# MainBOB_RUDRV2.net
KiCad netlist of a schematic drawn in Altium Designer
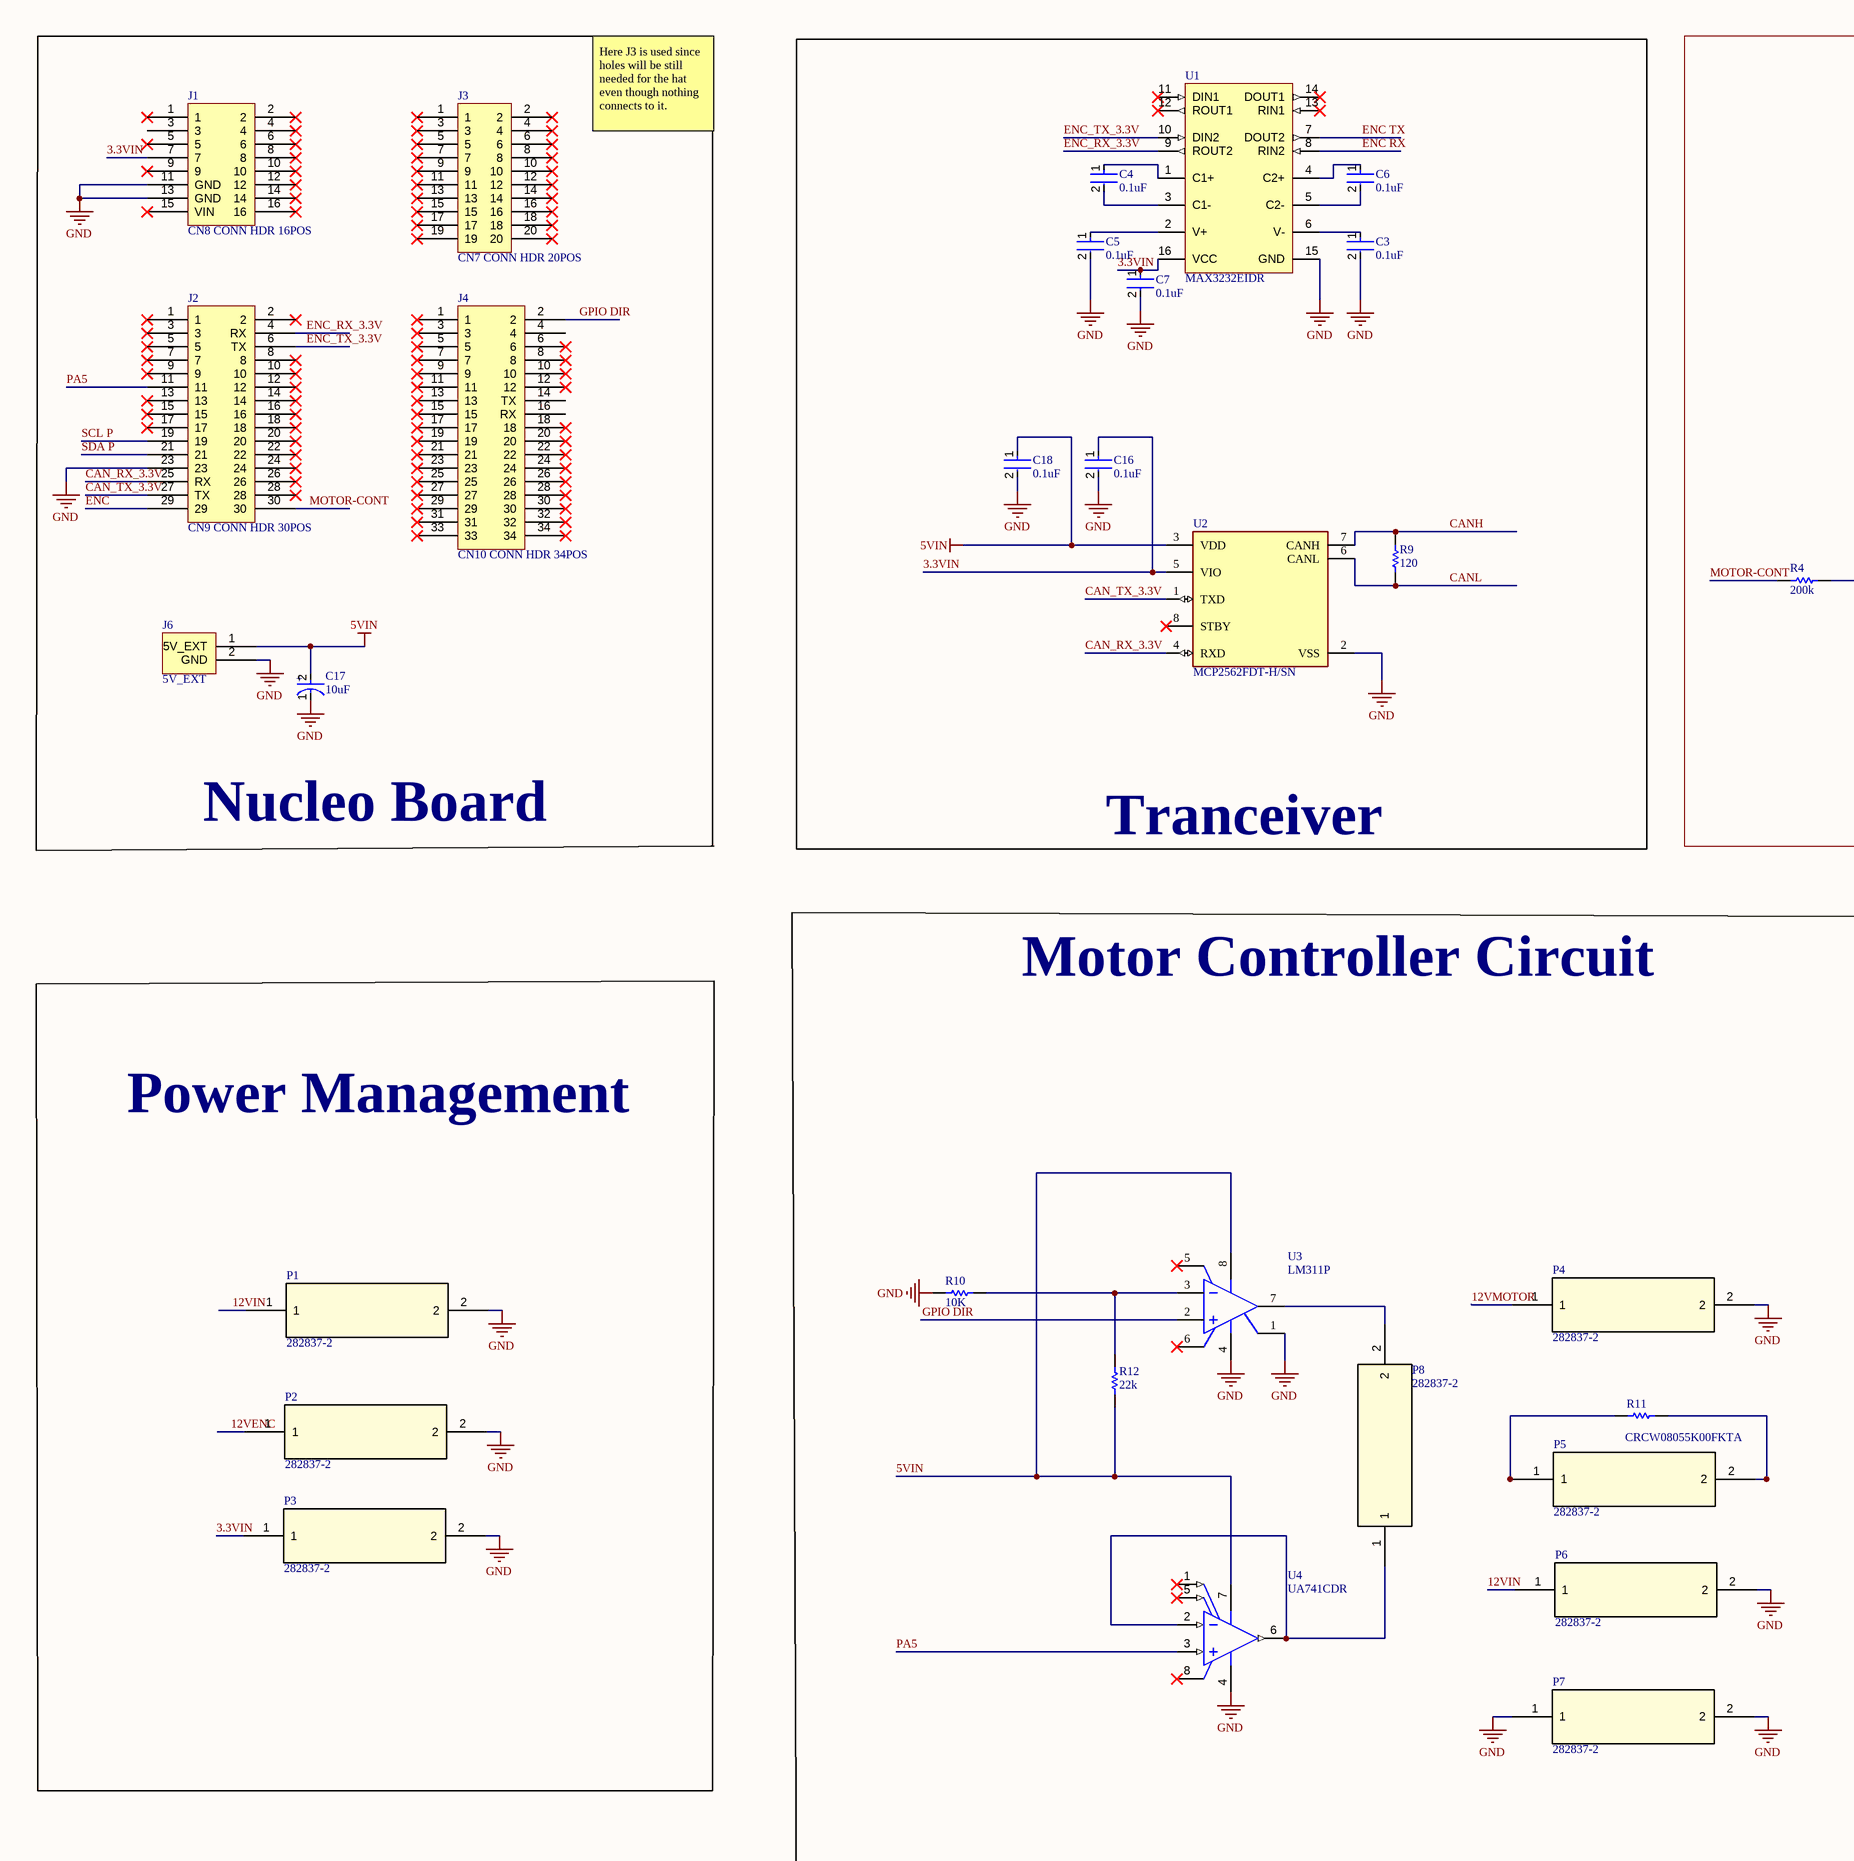
[diagram p0: MainBOB_RUDRV2.SchDoc, left]
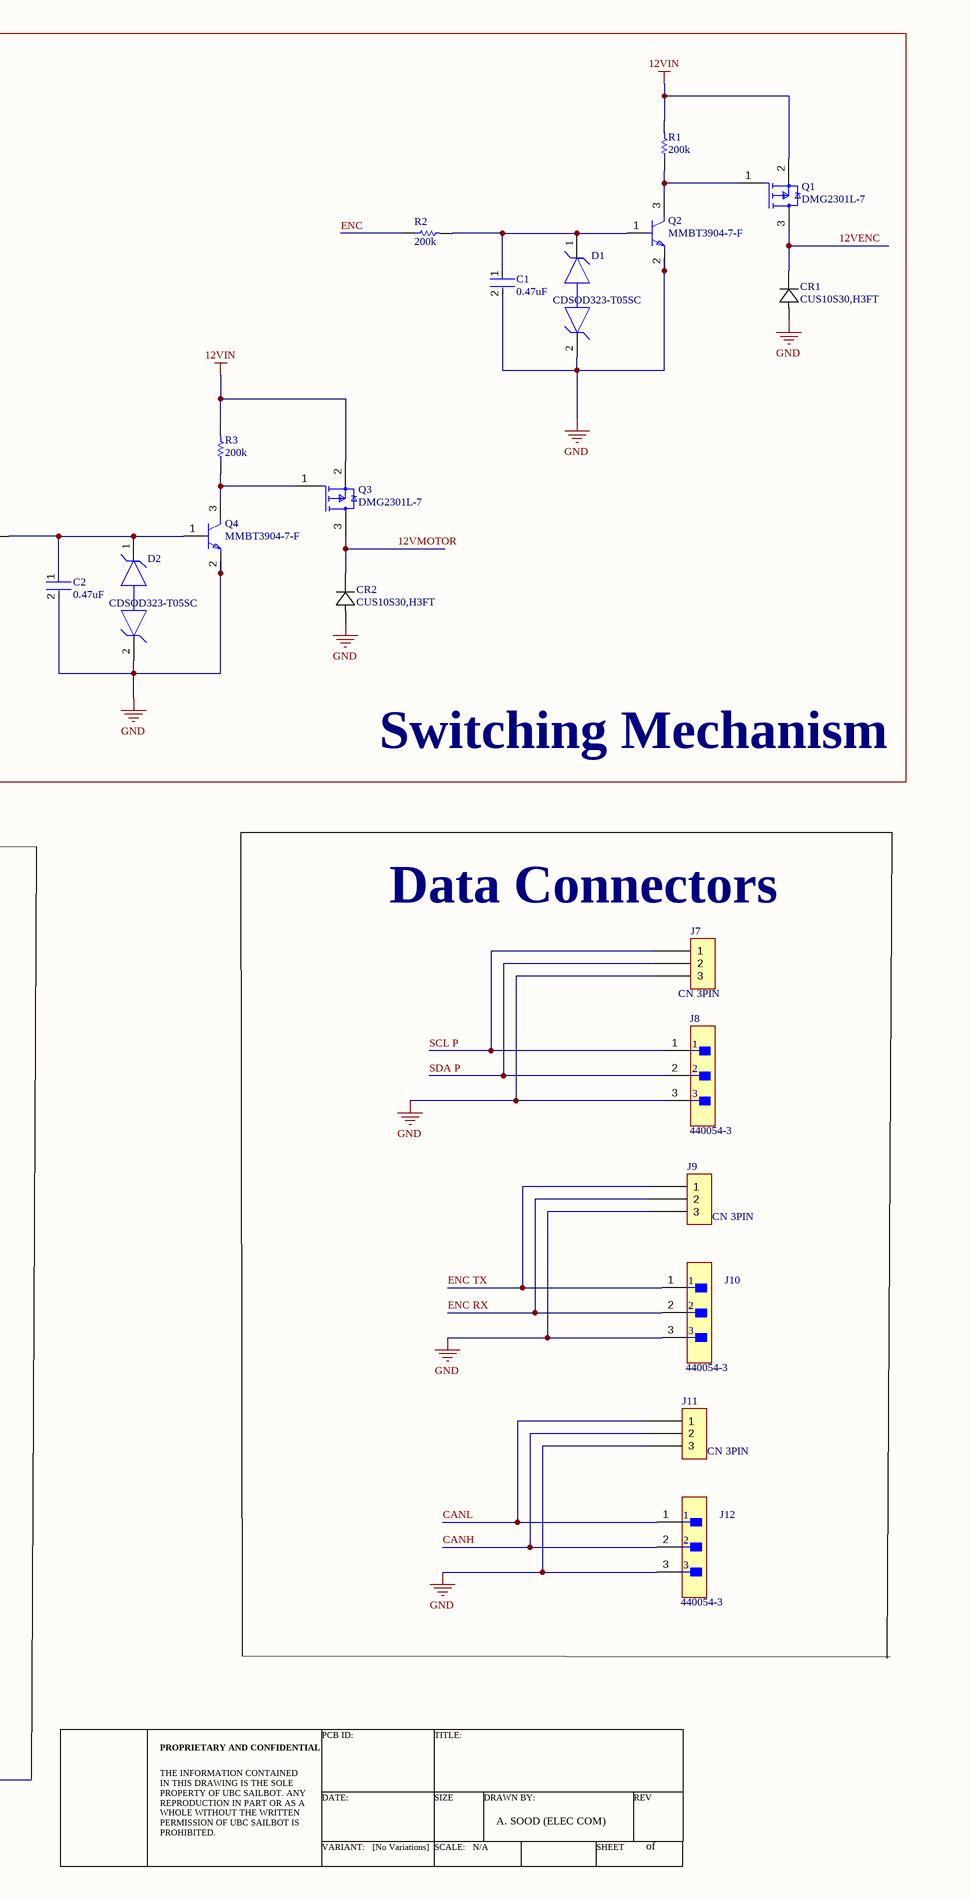
[diagram p1: MainBOB_RUDRV2.SchDoc, right]

(export (version "E")
  (design (tool "Eeschema 10.0.6"))
  (components
    (comp (ref "*") (value "Title Block") (libsource (lib "Schlib1") (part "Title Block")))
    (comp (ref "C1")
      (value "0.47uF")
      (footprint "FP-GRM21B-0_15-IPC_B")
      (description "Chip Multilayer Ceramic Capacitors for General Purpose, 0805, 0.47uF, X7R, 15%, 10%, 100V")
      (fields (field (name "VOLTAGE") "100V") (field (name "TOLERANCE") "10%"))
      (libsource (lib "Altium Content Vault") (part "b4654b650e69147ec39a6b967a45e02"))
    )
    (comp (ref "C2")
      (value "0.47uF")
      (footprint "FP-GRM21B-0_15-IPC_B")
      (description "Chip Multilayer Ceramic Capacitors for General Purpose, 0805, 0.47uF, X7R, 15%, 10%, 100V")
      (fields (field (name "VOLTAGE") "100V") (field (name "TOLERANCE") "10%"))
      (libsource (lib "Altium Content Vault") (part "b4654b650e69147ec39a6b967a45e02"))
    )
    (comp (ref "C3")
      (value "0.1uF")
      (footprint "FP-GCM21B-0_15-MFG")
      (description "Ceramic Capacitor for Automotive 100nF ±10% 100VDC X7R 0805 Embossed T/R")
      (fields (field (name "TOLERANCE") "10%") (field (name "VOLTAGE") "100V"))
      (libsource (lib "Altium Content Vault") (part "02cd4be3c70576c341d710602a673aa"))
    )
    (comp (ref "C4")
      (value "0.1uF")
      (footprint "FP-GCM21B-0_15-MFG")
      (description "Ceramic Capacitor for Automotive 100nF ±10% 100VDC X7R 0805 Embossed T/R")
      (fields (field (name "TOLERANCE") "10%") (field (name "VOLTAGE") "100V"))
      (libsource (lib "Altium Content Vault") (part "02cd4be3c70576c341d710602a673aa"))
    )
    (comp (ref "C5")
      (value "0.1uF")
      (footprint "FP-GCM21B-0_15-MFG")
      (description "Ceramic Capacitor for Automotive 100nF ±10% 100VDC X7R 0805 Embossed T/R")
      (fields (field (name "TOLERANCE") "10%") (field (name "VOLTAGE") "100V"))
      (libsource (lib "Altium Content Vault") (part "02cd4be3c70576c341d710602a673aa"))
    )
    (comp (ref "C6")
      (value "0.1uF")
      (footprint "FP-GCM21B-0_15-MFG")
      (description "Ceramic Capacitor for Automotive 100nF ±10% 100VDC X7R 0805 Embossed T/R")
      (fields (field (name "TOLERANCE") "10%") (field (name "VOLTAGE") "100V"))
      (libsource (lib "Altium Content Vault") (part "02cd4be3c70576c341d710602a673aa"))
    )
    (comp (ref "C7")
      (value "0.1uF")
      (footprint "FP-GCM21B-0_15-MFG")
      (description "Ceramic Capacitor for Automotive 100nF ±10% 100VDC X7R 0805 Embossed T/R")
      (fields (field (name "TOLERANCE") "10%") (field (name "VOLTAGE") "100V"))
      (libsource (lib "Altium Content Vault") (part "02cd4be3c70576c341d710602a673aa"))
    )
    (comp (ref "C16")
      (value "0.1uF")
      (footprint "FP-GCM21B-0_15-MFG")
      (description "Ceramic Capacitor for Automotive 100nF ±10% 100VDC X7R 0805 Embossed T/R")
      (fields (field (name "TOLERANCE") "10%") (field (name "VOLTAGE") "100V"))
      (libsource (lib "Altium Content Vault") (part "02cd4be3c70576c341d710602a673aa"))
    )
    (comp (ref "C17")
      (value "10uF")
      (footprint "FP-FKC-MFG")
      (description "CAP ALUM 10UF 20% 50V SMD")
      (fields (field (name "TOLERANCE") "20%") (field (name "VOLTAGE") "50V"))
      (libsource (lib "Altium Content Vault") (part "a00bbbee19879c290e62620ae7e47b1"))
    )
    (comp (ref "C18")
      (value "0.1uF")
      (footprint "FP-GCM21B-0_15-MFG")
      (description "Ceramic Capacitor for Automotive 100nF ±10% 100VDC X7R 0805 Embossed T/R")
      (fields (field (name "TOLERANCE") "10%") (field (name "VOLTAGE") "100V"))
      (libsource (lib "Altium Content Vault") (part "02cd4be3c70576c341d710602a673aa"))
    )
    (comp (ref "CR1")
      (value "CUS10S30,H3FT")
      (footprint "USC_TOS")
      (description "No Description Available")
      (libsource (lib "Schlib1") (part "CUS10S30,H3FT"))
    )
    (comp (ref "CR2")
      (value "CUS10S30,H3FT")
      (footprint "USC_TOS")
      (description "No Description Available")
      (libsource (lib "Schlib1") (part "CUS10S30,H3FT"))
    )
    (comp (ref "D1")
      (value "CDSOD323-T05SC")
      (footprint "FP-SOD-323-CA-MFG")
      (description "TVS DIODE 5VWM 14.5VC SOD323")
      (libsource (lib "Altium Content Vault") (part "c43c1b0add0eb72e36bdc657e82fc73"))
    )
    (comp (ref "D2")
      (value "CDSOD323-T05SC")
      (footprint "FP-SOD-323-CA-MFG")
      (description "TVS DIODE 5VWM 14.5VC SOD323")
      (libsource (lib "Altium Content Vault") (part "c43c1b0add0eb72e36bdc657e82fc73"))
    )
    (comp (ref "J1")
      (value "CN8 CONN HDR 16POS")
      (footprint "CN8_8X2_PADS")
      (description "CN8 CONN HDR 16POS 0.1 STACK")
      (libsource (lib "Schlib2") (part "CN8 CONN HDR 16POS"))
    )
    (comp (ref "J2")
      (value "CN9 CONN HDR 30POS")
      (footprint "CN9_15X2_PADS")
      (description "CN9 CONN HDR 30 POS  0.1 STACK")
      (libsource (lib "Schlib2") (part "CN9 CONN HDR 30POS"))
    )
    (comp (ref "J3")
      (value "CN7 CONN HDR 20POS")
      (footprint "CN7_10X2_PADS")
      (description "CN7 CONN HDR 20 POS  0.1 STACK")
      (libsource (lib "Schlib2") (part "CN7 CONN HDR 20POS"))
    )
    (comp (ref "J4")
      (value "CN10 CONN HDR 34POS")
      (footprint "CN10_17X2_PADS")
      (description "CN10 CONN HDR 34 POS  0.1 STACK")
      (libsource (lib "Schlib1") (part "CN10 CONN HDR 34POS"))
    )
    (comp (ref "J6") (value "5V_EXT") (footprint "5V_EXT") (libsource (lib "Schlib2") (part "5V_EXT")))
    (comp (ref "J7") (value "CN 3PIN") (footprint "3X1 CON") (libsource (lib "Schlib2") (part "CN 3PIN")))
    (comp (ref "J8")
      (value "440054-3")
      (footprint "FP-440054-3-MFG")
      (description "CONN HEADER VERT 3POS 2MM")
      (fields
        (field (name "OCTOPART") "https://octopart.com/440054-3-te+connectivity-40394845")
        (field (name "MANUFACTURER") "TE Connectivity")
      )
      (libsource (lib "Altium Content Vault") (part "0d3f023dd272f625e17a2be33dea85f"))
    )
    (comp (ref "J9") (value "CN 3PIN") (footprint "3X1 CON") (libsource (lib "Schlib2") (part "CN 3PIN")))
    (comp (ref "J10")
      (value "440054-3")
      (footprint "FP-440054-3-MFG")
      (description "CONN HEADER VERT 3POS 2MM")
      (fields
        (field (name "OCTOPART") "https://octopart.com/440054-3-te+connectivity-40394845")
        (field (name "MANUFACTURER") "TE Connectivity")
      )
      (libsource (lib "Altium Content Vault") (part "0d3f023dd272f625e17a2be33dea85f"))
    )
    (comp (ref "J11") (value "CN 3PIN") (footprint "3X1 CON") (libsource (lib "Schlib2") (part "CN 3PIN")))
    (comp (ref "J12")
      (value "440054-3")
      (footprint "FP-440054-3-MFG")
      (description "CONN HEADER VERT 3POS 2MM")
      (fields
        (field (name "OCTOPART") "https://octopart.com/440054-3-te+connectivity-40394845")
        (field (name "MANUFACTURER") "TE Connectivity")
      )
      (libsource (lib "Altium Content Vault") (part "0d3f023dd272f625e17a2be33dea85f"))
    )
    (comp (ref "P1")
      (value "282837-2")
      (footprint "282837-2_TYC")
      (description "No Description Available")
      (libsource (lib "Schlib1") (part "282837-2"))
    )
    (comp (ref "P2")
      (value "282837-2")
      (footprint "282837-2_TYC")
      (description "No Description Available")
      (libsource (lib "Schlib1") (part "282837-2"))
    )
    (comp (ref "P3")
      (value "282837-2")
      (footprint "282837-2_TYC")
      (description "No Description Available")
      (libsource (lib "Schlib1") (part "282837-2"))
    )
    (comp (ref "P4")
      (value "282837-2")
      (footprint "282837-2_TYC")
      (description "No Description Available")
      (libsource (lib "Schlib1") (part "282837-2"))
    )
    (comp (ref "P5")
      (value "282837-2")
      (footprint "282837-2_TYC")
      (description "No Description Available")
      (libsource (lib "Schlib1") (part "282837-2"))
    )
    (comp (ref "P6")
      (value "282837-2")
      (footprint "282837-2_TYC")
      (description "No Description Available")
      (libsource (lib "Schlib1") (part "282837-2"))
    )
    (comp (ref "P7")
      (value "282837-2")
      (footprint "282837-2_TYC")
      (description "No Description Available")
      (libsource (lib "Schlib1") (part "282837-2"))
    )
    (comp (ref "P8")
      (value "282837-2")
      (footprint "282837-2_TYC")
      (description "No Description Available")
      (libsource (lib "") (part "282837-2_1"))
    )
    (comp (ref "Q1")
      (value "DMG2301L-7")
      (footprint "FP-SOT23-MFG")
      (description "MOSFET P-CH 20V 3A SOT23")
      (fields
        (field (name "MANUFACTURER") "Diodes Inc.")
        (field (name "OCTOPART") "https://octopart.com/dmg2301l-7-diodes+inc.-67250456")
      )
      (libsource (lib "Altium Content Vault") (part "b8f99f9e586195791e7fb11725ebaeb"))
    )
    (comp (ref "Q2")
      (value "MMBT3904-7-F")
      (footprint "FP-SOT23-IPC_A")
      (description "TRANS NPN 40V 0.2A SMD SOT23-3")
      (libsource (lib "Altium Content Vault") (part "b44e953556f554d0102664c7d152cb4"))
    )
    (comp (ref "Q3")
      (value "DMG2301L-7")
      (footprint "FP-SOT23-MFG")
      (description "MOSFET P-CH 20V 3A SOT23")
      (fields
        (field (name "MANUFACTURER") "Diodes Inc.")
        (field (name "OCTOPART") "https://octopart.com/dmg2301l-7-diodes+inc.-67250456")
      )
      (libsource (lib "Altium Content Vault") (part "b8f99f9e586195791e7fb11725ebaeb"))
    )
    (comp (ref "Q4")
      (value "MMBT3904-7-F")
      (footprint "FP-SOT23-IPC_A")
      (description "TRANS NPN 40V 0.2A SMD SOT23-3")
      (libsource (lib "Altium Content Vault") (part "b44e953556f554d0102664c7d152cb4"))
    )
    (comp (ref "R1")
      (value "200k")
      (footprint "RESC2013X70X40LL20T20")
      (fields (field (name "MANUFACTURER") "Panasonic") (field (name "PART NUMBER") "ERJ-6ENF2003V"))
      (libsource (lib "Altium Content Vault") (part "RES"))
    )
    (comp (ref "R2")
      (value "200k")
      (footprint "RESC2013X70X40LL20T20")
      (fields (field (name "MANUFACTURER") "Panasonic") (field (name "PART NUMBER") "ERJ-6ENF2003V"))
      (libsource (lib "Altium Content Vault") (part "RES"))
    )
    (comp (ref "R3")
      (value "200k")
      (footprint "RESC2013X70X40LL20T20")
      (fields (field (name "MANUFACTURER") "Panasonic") (field (name "PART NUMBER") "ERJ-6ENF2003V"))
      (libsource (lib "Altium Content Vault") (part "RES"))
    )
    (comp (ref "R4")
      (value "200k")
      (footprint "RESC2013X70X40LL20T20")
      (fields (field (name "MANUFACTURER") "Panasonic") (field (name "PART NUMBER") "ERJ-6ENF2003V"))
      (libsource (lib "Altium Content Vault") (part "RES"))
    )
    (comp (ref "R9")
      (value "120")
      (footprint "RESC2013X60X35ML10T20")
      (description "Chip Resistor, 1 KOhm, +/- 1%, 125 mW, -55 to 155 degC, 0805 (2012 Metric), RoHS, Tape and Reel")
      (fields (field (name "TOLERANCE") "1%") (field (name "MANUFACTURER") "Yageo"))
      (libsource (lib "Altium Content Vault") (part "RES-2"))
    )
    (comp (ref "R10")
      (value "10K")
      (footprint "RESC2013X60X40LL20T25_A")
      (fields (field (name "TOLERANCE") "0.1%") (field (name "MANUFACTURER") "Panasonic"))
      (libsource (lib "Altium Content Vault") (part "RES-2"))
    )
    (comp (ref "R11")
      (value "CRCW08055K00FKTA")
      (footprint "RESC2013X50X30ML20T20")
      (fields (field (name "MANUFACTURER") "Vishay Dale"))
      (libsource (lib "Altium Content Vault") (part "RES"))
    )
    (comp (ref "R12")
      (value "22k")
      (footprint "RESC2013X60X40ML20T25")
      (fields (field (name "MANUFACTURER") "Panasonic") (field (name "PART NUMBER") "ERA6AEB223V"))
      (libsource (lib "Altium Content Vault") (part "RES"))
    )
    (comp (ref "U1")
      (value "MAX3232EIDR")
      (footprint "D0016A_N")
      (libsource (lib "Altium Content Vault") (part "TI-MAX3232E-SOIC_D-16"))
    )
    (comp (ref "U2")
      (value "MCP2562FDT-H/SN")
      (footprint "FP-C04-057-SN-IPC_A")
      (description "IC TRANSCEIVER 1/1 8SOIC")
      (libsource (lib "Altium Content Vault") (part "d4eccbb03d796c5d2cef85367bb866b"))
    )
    (comp (ref "U3")
      (value "LM311P")
      (footprint "FP-P0008A-MFG")
      (fields (field (name "TOLERANCE") "1%"))
      (libsource (lib "Altium Content Vault") (part "b2b1c66385073ed7f685b7e01cc60c1"))
    )
    (comp (ref "U4")
      (value "UA741CDR")
      (footprint "D0008A_L")
      (fields (field (name "MANUFACTURER") "Texas Instruments"))
      (libsource (lib "Altium Content Vault") (part "TI-AMP-S5-2-8"))
    )
  )
  (nets
    (net (code "1") (name "/3.3VIN") (class "Default")
      (node (ref "C16") (pin "1") (pinfunction "1_1") (pintype "passive"))
      (node (ref "C7") (pin "1") (pinfunction "1_1") (pintype "passive"))
      (node (ref "J1") (pin "7") (pinfunction "7_7") (pintype "passive"))
      (node (ref "P3") (pin "1") (pinfunction "1_1") (pintype "passive"))
      (node (ref "U1") (pin "16") (pinfunction "VCC_16") (pintype "power_in"))
      (node (ref "U2") (pin "5") (pinfunction "VIO_5") (pintype "power_in"))
    )
    (net (code "2") (name "/12VENC") (class "Default")
      (node (ref "CR1") (pin "1") (pinfunction "cathode_1") (pintype "passive"))
      (node (ref "P2") (pin "1") (pinfunction "1_1") (pintype "passive"))
      (node (ref "Q1") (pin "3") (pinfunction "D_3") (pintype "passive"))
    )
    (net (code "3") (name "/12VMOTOR") (class "Default")
      (node (ref "CR2") (pin "1") (pinfunction "cathode_1") (pintype "passive"))
      (node (ref "P4") (pin "1") (pinfunction "1_1") (pintype "passive"))
      (node (ref "Q3") (pin "3") (pinfunction "D_3") (pintype "passive"))
    )
    (net (code "4") (name "/CANH") (class "Default")
      (node (ref "J11") (pin "2") (pinfunction "2_2") (pintype "passive"))
      (node (ref "J12") (pin "2") (pinfunction "2_2") (pintype "passive"))
      (node (ref "R9") (pin "1") (pinfunction "1_1") (pintype "passive"))
      (node (ref "U2") (pin "7") (pinfunction "CANH_7") (pintype "passive"))
    )
    (net (code "5") (name "/CANL") (class "Default")
      (node (ref "J11") (pin "1") (pinfunction "1_1") (pintype "passive"))
      (node (ref "J12") (pin "1") (pinfunction "1_1") (pintype "passive"))
      (node (ref "R9") (pin "2") (pinfunction "2_2") (pintype "passive"))
      (node (ref "U2") (pin "6") (pinfunction "CANL_6") (pintype "passive"))
    )
    (net (code "6") (name "/CAN_RX_3.3V") (class "Default")
      (node (ref "J2") (pin "25") (pinfunction "RX_25") (pintype "passive"))
      (node (ref "U2") (pin "4") (pinfunction "RXD_4") (pintype "bidirectional"))
    )
    (net (code "7") (name "/CAN_TX_3.3V") (class "Default")
      (node (ref "J2") (pin "27") (pinfunction "TX_27") (pintype "passive"))
      (node (ref "U2") (pin "1") (pinfunction "TXD_1") (pintype "bidirectional"))
    )
    (net (code "8") (name "/ENC") (class "Default")
      (node (ref "J2") (pin "29") (pinfunction "29_29") (pintype "passive"))
      (node (ref "R2") (pin "1") (pinfunction "1_1") (pintype "passive"))
    )
    (net (code "9") (name "/ENC RX") (class "Default")
      (node (ref "J10") (pin "2") (pinfunction "2_2") (pintype "passive"))
      (node (ref "J9") (pin "2") (pinfunction "2_2") (pintype "passive"))
      (node (ref "U1") (pin "8") (pinfunction "RIN2_8") (pintype "input"))
    )
    (net (code "10") (name "/ENC TX") (class "Default")
      (node (ref "J10") (pin "1") (pinfunction "1_1") (pintype "passive"))
      (node (ref "J9") (pin "1") (pinfunction "1_1") (pintype "passive"))
      (node (ref "U1") (pin "7") (pinfunction "DOUT2_7") (pintype "output"))
    )
    (net (code "11") (name "/ENC_RX_3.3V") (class "Default")
      (node (ref "J2") (pin "4") (pinfunction "RX_4") (pintype "passive"))
      (node (ref "U1") (pin "9") (pinfunction "ROUT2_9") (pintype "output"))
    )
    (net (code "12") (name "/ENC_TX_3.3V") (class "Default")
      (node (ref "J2") (pin "6") (pinfunction "TX_6") (pintype "passive"))
      (node (ref "U1") (pin "10") (pinfunction "DIN2_10") (pintype "input"))
    )
    (net (code "13") (name "/GPIO DIR") (class "Default")
      (node (ref "J4") (pin "2") (pinfunction "2_2") (pintype "passive"))
      (node (ref "U3") (pin "2") (pinfunction "IN+_2") (pintype "tri_state"))
    )
    (net (code "14") (name "/MOTOR-CONT") (class "Default")
      (node (ref "J2") (pin "30") (pinfunction "30_30") (pintype "passive"))
      (node (ref "R4") (pin "1") (pinfunction "1_1") (pintype "passive"))
    )
    (net (code "15") (name "/PA5") (class "Default")
      (node (ref "J2") (pin "11") (pinfunction "11_11") (pintype "passive"))
      (node (ref "U4") (pin "3") (pinfunction "IN+_3") (pintype "input"))
    )
    (net (code "16") (name "/SCL P") (class "Default")
      (node (ref "J2") (pin "19") (pinfunction "19_19") (pintype "passive"))
      (node (ref "J7") (pin "1") (pinfunction "1_1") (pintype "passive"))
      (node (ref "J8") (pin "1") (pinfunction "1_1") (pintype "passive"))
    )
    (net (code "17") (name "/SDA P") (class "Default")
      (node (ref "J2") (pin "21") (pinfunction "21_21") (pintype "passive"))
      (node (ref "J7") (pin "2") (pinfunction "2_2") (pintype "passive"))
      (node (ref "J8") (pin "2") (pinfunction "2_2") (pintype "passive"))
    )
    (net (code "18") (name "5VIN") (class "Default")
      (node (ref "C17") (pin "2") (pinfunction "A_2") (pintype "passive"))
      (node (ref "C18") (pin "1") (pinfunction "1_1") (pintype "passive"))
      (node (ref "J6") (pin "1") (pinfunction "5V_EXT_1") (pintype "passive"))
      (node (ref "R12") (pin "1") (pinfunction "1_1") (pintype "passive"))
      (node (ref "U2") (pin "3") (pinfunction "VDD_3") (pintype "power_in"))
      (node (ref "U3") (pin "8") (pinfunction "VCC+_8") (pintype "power_in"))
      (node (ref "U4") (pin "7") (pinfunction "VCC+_7") (pintype "power_in"))
    )
    (net (code "19") (name "12VIN") (class "Default")
      (node (ref "P1") (pin "1") (pinfunction "1_1") (pintype "passive"))
      (node (ref "P6") (pin "1") (pinfunction "1_1") (pintype "passive"))
      (node (ref "Q1") (pin "2") (pinfunction "S_2") (pintype "passive"))
      (node (ref "Q3") (pin "2") (pinfunction "S_2") (pintype "passive"))
      (node (ref "R1") (pin "2") (pinfunction "2_2") (pintype "passive"))
      (node (ref "R3") (pin "2") (pinfunction "2_2") (pintype "passive"))
    )
    (net (code "20") (name "GND") (class "Default")
      (node (ref "C1") (pin "2") (pinfunction "2_2") (pintype "passive"))
      (node (ref "C16") (pin "2") (pinfunction "2_2") (pintype "passive"))
      (node (ref "C17") (pin "1") (pinfunction "C_1") (pintype "passive"))
      (node (ref "C18") (pin "2") (pinfunction "2_2") (pintype "passive"))
      (node (ref "C2") (pin "2") (pinfunction "2_2") (pintype "passive"))
      (node (ref "C3") (pin "2") (pinfunction "2_2") (pintype "passive"))
      (node (ref "C5") (pin "2") (pinfunction "2_2") (pintype "passive"))
      (node (ref "C7") (pin "2") (pinfunction "2_2") (pintype "passive"))
      (node (ref "CR1") (pin "2") (pinfunction "anode_2") (pintype "passive"))
      (node (ref "CR2") (pin "2") (pinfunction "anode_2") (pintype "passive"))
      (node (ref "D1") (pin "2") (pinfunction "2_2") (pintype "passive"))
      (node (ref "D2") (pin "2") (pinfunction "2_2") (pintype "passive"))
      (node (ref "J1") (pin "11") (pinfunction "GND_11") (pintype "passive"))
      (node (ref "J1") (pin "13") (pinfunction "GND_13") (pintype "passive"))
      (node (ref "J10") (pin "3") (pinfunction "3_3") (pintype "passive"))
      (node (ref "J11") (pin "3") (pinfunction "3_3") (pintype "passive"))
      (node (ref "J12") (pin "3") (pinfunction "3_3") (pintype "passive"))
      (node (ref "J2") (pin "23") (pinfunction "23_23") (pintype "passive"))
      (node (ref "J6") (pin "2") (pinfunction "GND_2") (pintype "passive"))
      (node (ref "J7") (pin "3") (pinfunction "3_3") (pintype "passive"))
      (node (ref "J8") (pin "3") (pinfunction "3_3") (pintype "passive"))
      (node (ref "J9") (pin "3") (pinfunction "3_3") (pintype "passive"))
      (node (ref "P1") (pin "2") (pinfunction "2_2") (pintype "passive"))
      (node (ref "P2") (pin "2") (pinfunction "2_2") (pintype "passive"))
      (node (ref "P3") (pin "2") (pinfunction "2_2") (pintype "passive"))
      (node (ref "P4") (pin "2") (pinfunction "2_2") (pintype "passive"))
      (node (ref "P6") (pin "2") (pinfunction "2_2") (pintype "passive"))
      (node (ref "P7") (pin "1") (pinfunction "1_1") (pintype "passive"))
      (node (ref "P7") (pin "2") (pinfunction "2_2") (pintype "passive"))
      (node (ref "Q2") (pin "2") (pinfunction "E_2") (pintype "passive"))
      (node (ref "Q4") (pin "2") (pinfunction "E_2") (pintype "passive"))
      (node (ref "R10") (pin "1") (pinfunction "1_1") (pintype "passive"))
      (node (ref "U1") (pin "15") (pinfunction "GND_15") (pintype "power_in"))
      (node (ref "U2") (pin "2") (pinfunction "VSS_2") (pintype "power_in"))
      (node (ref "U3") (pin "1") (pinfunction "EMIT_OUT_1") (pintype "open_emitter"))
      (node (ref "U3") (pin "4") (pinfunction "VCC-_4") (pintype "power_in"))
      (node (ref "U4") (pin "4") (pinfunction "VCC-_4") (pintype "power_in"))
    )
    (net (code "21") (name "Net-(P5-Pad1)") (class "Default")
      (node (ref "P5") (pin "1") (pinfunction "1_1") (pintype "passive"))
      (node (ref "R11") (pin "1") (pinfunction "1_1") (pintype "passive"))
    )
    (net (code "22") (name "Net-(P5-Pad2)") (class "Default")
      (node (ref "P5") (pin "2") (pinfunction "2_2") (pintype "passive"))
      (node (ref "R11") (pin "2") (pinfunction "2_2") (pintype "passive"))
    )
    (net (code "23") (name "Net-(Q1-G)") (class "Default")
      (node (ref "Q1") (pin "1") (pinfunction "G_1") (pintype "passive"))
      (node (ref "Q2") (pin "3") (pinfunction "C_3") (pintype "passive"))
      (node (ref "R1") (pin "1") (pinfunction "1_1") (pintype "passive"))
    )
    (net (code "24") (name "Net-(Q2-B)") (class "Default")
      (node (ref "C1") (pin "1") (pinfunction "1_1") (pintype "passive"))
      (node (ref "D1") (pin "1") (pinfunction "1_1") (pintype "passive"))
      (node (ref "Q2") (pin "1") (pinfunction "B_1") (pintype "passive"))
      (node (ref "R2") (pin "2") (pinfunction "2_2") (pintype "passive"))
    )
    (net (code "25") (name "Net-(Q3-G)") (class "Default")
      (node (ref "Q3") (pin "1") (pinfunction "G_1") (pintype "passive"))
      (node (ref "Q4") (pin "3") (pinfunction "C_3") (pintype "passive"))
      (node (ref "R3") (pin "1") (pinfunction "1_1") (pintype "passive"))
    )
    (net (code "26") (name "Net-(Q4-B)") (class "Default")
      (node (ref "C2") (pin "1") (pinfunction "1_1") (pintype "passive"))
      (node (ref "D2") (pin "1") (pinfunction "1_1") (pintype "passive"))
      (node (ref "Q4") (pin "1") (pinfunction "B_1") (pintype "passive"))
      (node (ref "R4") (pin "2") (pinfunction "2_2") (pintype "passive"))
    )
    (net (code "27") (name "Net-(U1-C1+)") (class "Default")
      (node (ref "C4") (pin "1") (pinfunction "1_1") (pintype "passive"))
      (node (ref "U1") (pin "1") (pinfunction "C1+_1") (pintype "passive"))
    )
    (net (code "28") (name "Net-(U1-C1-)") (class "Default")
      (node (ref "C4") (pin "2") (pinfunction "2_2") (pintype "passive"))
      (node (ref "U1") (pin "3") (pinfunction "C1-_3") (pintype "passive"))
    )
    (net (code "29") (name "Net-(U1-C2+)") (class "Default")
      (node (ref "C6") (pin "1") (pinfunction "1_1") (pintype "passive"))
      (node (ref "U1") (pin "4") (pinfunction "C2+_4") (pintype "passive"))
    )
    (net (code "30") (name "Net-(U1-C2-)") (class "Default")
      (node (ref "C6") (pin "2") (pinfunction "2_2") (pintype "passive"))
      (node (ref "U1") (pin "5") (pinfunction "C2-_5") (pintype "passive"))
    )
    (net (code "31") (name "Net-(U1-V+)") (class "Default")
      (node (ref "C5") (pin "1") (pinfunction "1_1") (pintype "passive"))
      (node (ref "U1") (pin "2") (pinfunction "V+_2") (pintype "power_in"))
    )
    (net (code "32") (name "Net-(U1-V-)") (class "Default")
      (node (ref "C3") (pin "1") (pinfunction "1_1") (pintype "passive"))
      (node (ref "U1") (pin "6") (pinfunction "V-_6") (pintype "power_in"))
    )
    (net (code "33") (name "Net-(U3-COL_OUT)") (class "Default")
      (node (ref "P8") (pin "2") (pinfunction "2_2") (pintype "passive"))
      (node (ref "U3") (pin "7") (pinfunction "COL_OUT_7") (pintype "open_collector"))
    )
    (net (code "34") (name "Net-(U3-IN-)") (class "Default")
      (node (ref "R10") (pin "2") (pinfunction "2_2") (pintype "passive"))
      (node (ref "R12") (pin "2") (pinfunction "2_2") (pintype "passive"))
      (node (ref "U3") (pin "3") (pinfunction "IN-_3") (pintype "tri_state"))
    )
    (net (code "35") (name "Net-(U4-IN-)") (class "Default")
      (node (ref "P8") (pin "1") (pinfunction "1_1") (pintype "passive"))
      (node (ref "U4") (pin "2") (pinfunction "IN-_2") (pintype "input"))
      (node (ref "U4") (pin "6") (pinfunction "OUT_6") (pintype "output"))
    )
    (net (code "36") (name "unconnected-(J1-Pad1)") (class "Default")
      (node (ref "J1") (pin "1") (pinfunction "1_1") (pintype "passive+no_connect"))
    )
    (net (code "37") (name "unconnected-(J1-Pad2)") (class "Default")
      (node (ref "J1") (pin "2") (pinfunction "2_2") (pintype "passive+no_connect"))
    )
    (net (code "38") (name "unconnected-(J1-Pad3)") (class "Default")
      (node (ref "J1") (pin "3") (pinfunction "3_3") (pintype "passive"))
    )
    (net (code "39") (name "unconnected-(J1-Pad4)") (class "Default")
      (node (ref "J1") (pin "4") (pinfunction "4_4") (pintype "passive+no_connect"))
    )
    (net (code "40") (name "unconnected-(J1-Pad5)") (class "Default")
      (node (ref "J1") (pin "5") (pinfunction "5_5") (pintype "passive+no_connect"))
    )
    (net (code "41") (name "unconnected-(J1-Pad6)") (class "Default")
      (node (ref "J1") (pin "6") (pinfunction "6_6") (pintype "passive+no_connect"))
    )
    (net (code "42") (name "unconnected-(J1-Pad8)") (class "Default")
      (node (ref "J1") (pin "8") (pinfunction "8_8") (pintype "passive+no_connect"))
    )
    (net (code "43") (name "unconnected-(J1-Pad9)") (class "Default")
      (node (ref "J1") (pin "9") (pinfunction "9_9") (pintype "passive+no_connect"))
    )
    (net (code "44") (name "unconnected-(J1-Pad10)") (class "Default")
      (node (ref "J1") (pin "10") (pinfunction "10_10") (pintype "passive+no_connect"))
    )
    (net (code "45") (name "unconnected-(J1-Pad12)") (class "Default")
      (node (ref "J1") (pin "12") (pinfunction "12_12") (pintype "passive+no_connect"))
    )
    (net (code "46") (name "unconnected-(J1-Pad14)") (class "Default")
      (node (ref "J1") (pin "14") (pinfunction "14_14") (pintype "passive+no_connect"))
    )
    (net (code "47") (name "unconnected-(J1-Pad16)") (class "Default")
      (node (ref "J1") (pin "16") (pinfunction "16_16") (pintype "passive+no_connect"))
    )
    (net (code "48") (name "unconnected-(J1-VIN-Pad15)") (class "Default")
      (node (ref "J1") (pin "15") (pinfunction "VIN_15") (pintype "passive+no_connect"))
    )
    (net (code "49") (name "unconnected-(J2-Pad1)") (class "Default")
      (node (ref "J2") (pin "1") (pinfunction "1_1") (pintype "passive+no_connect"))
    )
    (net (code "50") (name "unconnected-(J2-Pad2)") (class "Default")
      (node (ref "J2") (pin "2") (pinfunction "2_2") (pintype "passive+no_connect"))
    )
    (net (code "51") (name "unconnected-(J2-Pad3)") (class "Default")
      (node (ref "J2") (pin "3") (pinfunction "3_3") (pintype "passive+no_connect"))
    )
    (net (code "52") (name "unconnected-(J2-Pad5)") (class "Default")
      (node (ref "J2") (pin "5") (pinfunction "5_5") (pintype "passive+no_connect"))
    )
    (net (code "53") (name "unconnected-(J2-Pad7)") (class "Default")
      (node (ref "J2") (pin "7") (pinfunction "7_7") (pintype "passive+no_connect"))
    )
    (net (code "54") (name "unconnected-(J2-Pad8)") (class "Default")
      (node (ref "J2") (pin "8") (pinfunction "8_8") (pintype "passive+no_connect"))
    )
    (net (code "55") (name "unconnected-(J2-Pad9)") (class "Default")
      (node (ref "J2") (pin "9") (pinfunction "9_9") (pintype "passive+no_connect"))
    )
    (net (code "56") (name "unconnected-(J2-Pad10)") (class "Default")
      (node (ref "J2") (pin "10") (pinfunction "10_10") (pintype "passive+no_connect"))
    )
    (net (code "57") (name "unconnected-(J2-Pad12)") (class "Default")
      (node (ref "J2") (pin "12") (pinfunction "12_12") (pintype "passive+no_connect"))
    )
    (net (code "58") (name "unconnected-(J2-Pad13)") (class "Default")
      (node (ref "J2") (pin "13") (pinfunction "13_13") (pintype "passive+no_connect"))
    )
    (net (code "59") (name "unconnected-(J2-Pad14)") (class "Default")
      (node (ref "J2") (pin "14") (pinfunction "14_14") (pintype "passive+no_connect"))
    )
    (net (code "60") (name "unconnected-(J2-Pad15)") (class "Default")
      (node (ref "J2") (pin "15") (pinfunction "15_15") (pintype "passive+no_connect"))
    )
    (net (code "61") (name "unconnected-(J2-Pad16)") (class "Default")
      (node (ref "J2") (pin "16") (pinfunction "16_16") (pintype "passive+no_connect"))
    )
    (net (code "62") (name "unconnected-(J2-Pad17)") (class "Default")
      (node (ref "J2") (pin "17") (pinfunction "17_17") (pintype "passive+no_connect"))
    )
    (net (code "63") (name "unconnected-(J2-Pad18)") (class "Default")
      (node (ref "J2") (pin "18") (pinfunction "18_18") (pintype "passive+no_connect"))
    )
    (net (code "64") (name "unconnected-(J2-Pad20)") (class "Default")
      (node (ref "J2") (pin "20") (pinfunction "20_20") (pintype "passive+no_connect"))
    )
    (net (code "65") (name "unconnected-(J2-Pad22)") (class "Default")
      (node (ref "J2") (pin "22") (pinfunction "22_22") (pintype "passive+no_connect"))
    )
    (net (code "66") (name "unconnected-(J2-Pad24)") (class "Default")
      (node (ref "J2") (pin "24") (pinfunction "24_24") (pintype "passive+no_connect"))
    )
    (net (code "67") (name "unconnected-(J2-Pad26)") (class "Default")
      (node (ref "J2") (pin "26") (pinfunction "26_26") (pintype "passive+no_connect"))
    )
    (net (code "68") (name "unconnected-(J2-Pad28)") (class "Default")
      (node (ref "J2") (pin "28") (pinfunction "28_28") (pintype "passive+no_connect"))
    )
    (net (code "69") (name "unconnected-(J3-Pad1)") (class "Default")
      (node (ref "J3") (pin "1") (pinfunction "1_1") (pintype "passive+no_connect"))
    )
    (net (code "70") (name "unconnected-(J3-Pad2)") (class "Default")
      (node (ref "J3") (pin "2") (pinfunction "2_2") (pintype "passive+no_connect"))
    )
    (net (code "71") (name "unconnected-(J3-Pad3)") (class "Default")
      (node (ref "J3") (pin "3") (pinfunction "3_3") (pintype "passive+no_connect"))
    )
    (net (code "72") (name "unconnected-(J3-Pad4)") (class "Default")
      (node (ref "J3") (pin "4") (pinfunction "4_4") (pintype "passive+no_connect"))
    )
    (net (code "73") (name "unconnected-(J3-Pad5)") (class "Default")
      (node (ref "J3") (pin "5") (pinfunction "5_5") (pintype "passive+no_connect"))
    )
    (net (code "74") (name "unconnected-(J3-Pad6)") (class "Default")
      (node (ref "J3") (pin "6") (pinfunction "6_6") (pintype "passive+no_connect"))
    )
    (net (code "75") (name "unconnected-(J3-Pad7)") (class "Default")
      (node (ref "J3") (pin "7") (pinfunction "7_7") (pintype "passive+no_connect"))
    )
    (net (code "76") (name "unconnected-(J3-Pad8)") (class "Default")
      (node (ref "J3") (pin "8") (pinfunction "8_8") (pintype "passive+no_connect"))
    )
    (net (code "77") (name "unconnected-(J3-Pad9)") (class "Default")
      (node (ref "J3") (pin "9") (pinfunction "9_9") (pintype "passive+no_connect"))
    )
    (net (code "78") (name "unconnected-(J3-Pad10)") (class "Default")
      (node (ref "J3") (pin "10") (pinfunction "10_10") (pintype "passive+no_connect"))
    )
    (net (code "79") (name "unconnected-(J3-Pad11)") (class "Default")
      (node (ref "J3") (pin "11") (pinfunction "11_11") (pintype "passive+no_connect"))
    )
    (net (code "80") (name "unconnected-(J3-Pad12)") (class "Default")
      (node (ref "J3") (pin "12") (pinfunction "12_12") (pintype "passive+no_connect"))
    )
    (net (code "81") (name "unconnected-(J3-Pad13)") (class "Default")
      (node (ref "J3") (pin "13") (pinfunction "13_13") (pintype "passive+no_connect"))
    )
    (net (code "82") (name "unconnected-(J3-Pad14)") (class "Default")
      (node (ref "J3") (pin "14") (pinfunction "14_14") (pintype "passive+no_connect"))
    )
    (net (code "83") (name "unconnected-(J3-Pad15)") (class "Default")
      (node (ref "J3") (pin "15") (pinfunction "15_15") (pintype "passive+no_connect"))
    )
    (net (code "84") (name "unconnected-(J3-Pad16)") (class "Default")
      (node (ref "J3") (pin "16") (pinfunction "16_16") (pintype "passive+no_connect"))
    )
    (net (code "85") (name "unconnected-(J3-Pad17)") (class "Default")
      (node (ref "J3") (pin "17") (pinfunction "17_17") (pintype "passive+no_connect"))
    )
    (net (code "86") (name "unconnected-(J3-Pad18)") (class "Default")
      (node (ref "J3") (pin "18") (pinfunction "18_18") (pintype "passive+no_connect"))
    )
    (net (code "87") (name "unconnected-(J3-Pad19)") (class "Default")
      (node (ref "J3") (pin "19") (pinfunction "19_19") (pintype "passive+no_connect"))
    )
    (net (code "88") (name "unconnected-(J3-Pad20)") (class "Default")
      (node (ref "J3") (pin "20") (pinfunction "20_20") (pintype "passive+no_connect"))
    )
    (net (code "89") (name "unconnected-(J4-Pad1)") (class "Default")
      (node (ref "J4") (pin "1") (pinfunction "1_1") (pintype "passive+no_connect"))
    )
    (net (code "90") (name "unconnected-(J4-Pad3)") (class "Default")
      (node (ref "J4") (pin "3") (pinfunction "3_3") (pintype "passive+no_connect"))
    )
    (net (code "91") (name "unconnected-(J4-Pad4)") (class "Default")
      (node (ref "J4") (pin "4") (pinfunction "4_4") (pintype "passive"))
    )
    (net (code "92") (name "unconnected-(J4-Pad5)") (class "Default")
      (node (ref "J4") (pin "5") (pinfunction "5_5") (pintype "passive+no_connect"))
    )
    (net (code "93") (name "unconnected-(J4-Pad6)") (class "Default")
      (node (ref "J4") (pin "6") (pinfunction "6_6") (pintype "passive+no_connect"))
    )
    (net (code "94") (name "unconnected-(J4-Pad7)") (class "Default")
      (node (ref "J4") (pin "7") (pinfunction "7_7") (pintype "passive+no_connect"))
    )
    (net (code "95") (name "unconnected-(J4-Pad8)") (class "Default")
      (node (ref "J4") (pin "8") (pinfunction "8_8") (pintype "passive+no_connect"))
    )
    (net (code "96") (name "unconnected-(J4-Pad9)") (class "Default")
      (node (ref "J4") (pin "9") (pinfunction "9_9") (pintype "passive+no_connect"))
    )
    (net (code "97") (name "unconnected-(J4-Pad10)") (class "Default")
      (node (ref "J4") (pin "10") (pinfunction "10_10") (pintype "passive+no_connect"))
    )
    (net (code "98") (name "unconnected-(J4-Pad11)") (class "Default")
      (node (ref "J4") (pin "11") (pinfunction "11_11") (pintype "passive+no_connect"))
    )
    (net (code "99") (name "unconnected-(J4-Pad12)") (class "Default")
      (node (ref "J4") (pin "12") (pinfunction "12_12") (pintype "passive+no_connect"))
    )
    (net (code "100") (name "unconnected-(J4-Pad13)") (class "Default")
      (node (ref "J4") (pin "13") (pinfunction "13_13") (pintype "passive+no_connect"))
    )
    (net (code "101") (name "unconnected-(J4-Pad15)") (class "Default")
      (node (ref "J4") (pin "15") (pinfunction "15_15") (pintype "passive+no_connect"))
    )
    (net (code "102") (name "unconnected-(J4-Pad17)") (class "Default")
      (node (ref "J4") (pin "17") (pinfunction "17_17") (pintype "passive+no_connect"))
    )
    (net (code "103") (name "unconnected-(J4-Pad18)") (class "Default")
      (node (ref "J4") (pin "18") (pinfunction "18_18") (pintype "passive+no_connect"))
    )
    (net (code "104") (name "unconnected-(J4-Pad19)") (class "Default")
      (node (ref "J4") (pin "19") (pinfunction "19_19") (pintype "passive+no_connect"))
    )
    (net (code "105") (name "unconnected-(J4-Pad20)") (class "Default")
      (node (ref "J4") (pin "20") (pinfunction "20_20") (pintype "passive+no_connect"))
    )
    (net (code "106") (name "unconnected-(J4-Pad21)") (class "Default")
      (node (ref "J4") (pin "21") (pinfunction "21_21") (pintype "passive+no_connect"))
    )
    (net (code "107") (name "unconnected-(J4-Pad22)") (class "Default")
      (node (ref "J4") (pin "22") (pinfunction "22_22") (pintype "passive+no_connect"))
    )
    (net (code "108") (name "unconnected-(J4-Pad23)") (class "Default")
      (node (ref "J4") (pin "23") (pinfunction "23_23") (pintype "passive+no_connect"))
    )
    (net (code "109") (name "unconnected-(J4-Pad24)") (class "Default")
      (node (ref "J4") (pin "24") (pinfunction "24_24") (pintype "passive+no_connect"))
    )
    (net (code "110") (name "unconnected-(J4-Pad25)") (class "Default")
      (node (ref "J4") (pin "25") (pinfunction "25_25") (pintype "passive+no_connect"))
    )
    (net (code "111") (name "unconnected-(J4-Pad26)") (class "Default")
      (node (ref "J4") (pin "26") (pinfunction "26_26") (pintype "passive+no_connect"))
    )
    (net (code "112") (name "unconnected-(J4-Pad27)") (class "Default")
      (node (ref "J4") (pin "27") (pinfunction "27_27") (pintype "passive+no_connect"))
    )
    (net (code "113") (name "unconnected-(J4-Pad28)") (class "Default")
      (node (ref "J4") (pin "28") (pinfunction "28_28") (pintype "passive+no_connect"))
    )
    (net (code "114") (name "unconnected-(J4-Pad29)") (class "Default")
      (node (ref "J4") (pin "29") (pinfunction "29_29") (pintype "passive+no_connect"))
    )
    (net (code "115") (name "unconnected-(J4-Pad30)") (class "Default")
      (node (ref "J4") (pin "30") (pinfunction "30_30") (pintype "passive+no_connect"))
    )
    (net (code "116") (name "unconnected-(J4-Pad31)") (class "Default")
      (node (ref "J4") (pin "31") (pinfunction "31_31") (pintype "passive+no_connect"))
    )
    (net (code "117") (name "unconnected-(J4-Pad32)") (class "Default")
      (node (ref "J4") (pin "32") (pinfunction "32_32") (pintype "passive+no_connect"))
    )
    (net (code "118") (name "unconnected-(J4-Pad33)") (class "Default")
      (node (ref "J4") (pin "33") (pinfunction "33_33") (pintype "passive+no_connect"))
    )
    (net (code "119") (name "unconnected-(J4-Pad34)") (class "Default")
      (node (ref "J4") (pin "34") (pinfunction "34_34") (pintype "passive+no_connect"))
    )
    (net (code "120") (name "unconnected-(J4-RX-Pad16)") (class "Default")
      (node (ref "J4") (pin "16") (pinfunction "RX_16") (pintype "passive"))
    )
    (net (code "121") (name "unconnected-(J4-TX-Pad14)") (class "Default")
      (node (ref "J4") (pin "14") (pinfunction "TX_14") (pintype "passive"))
    )
    (net (code "122") (name "unconnected-(U1-DIN1-Pad11)") (class "Default")
      (node (ref "U1") (pin "11") (pinfunction "DIN1_11") (pintype "input+no_connect"))
    )
    (net (code "123") (name "unconnected-(U1-DOUT1-Pad14)") (class "Default")
      (node (ref "U1") (pin "14") (pinfunction "DOUT1_14") (pintype "output+no_connect"))
    )
    (net (code "124") (name "unconnected-(U1-RIN1-Pad13)") (class "Default")
      (node (ref "U1") (pin "13") (pinfunction "RIN1_13") (pintype "input+no_connect"))
    )
    (net (code "125") (name "unconnected-(U1-ROUT1-Pad12)") (class "Default")
      (node (ref "U1") (pin "12") (pinfunction "ROUT1_12") (pintype "output+no_connect"))
    )
    (net (code "126") (name "unconnected-(U2-STBY-Pad8)") (class "Default")
      (node (ref "U2") (pin "8") (pinfunction "STBY_8") (pintype "passive+no_connect"))
    )
    (net (code "127") (name "unconnected-(U3-BALANCE-Pad5)") (class "Default")
      (node (ref "U3") (pin "5") (pinfunction "BALANCE_5") (pintype "passive+no_connect"))
    )
    (net (code "128") (name "unconnected-(U3-BAL{slash}STRB-Pad6)") (class "Default")
      (node (ref "U3") (pin "6") (pinfunction "BAL/STRB_6") (pintype "passive+no_connect"))
    )
    (net (code "129") (name "unconnected-(U4-NC-Pad8)") (class "Default")
      (node (ref "U4") (pin "8") (pinfunction "NC_8") (pintype "passive+no_connect"))
    )
    (net (code "130") (name "unconnected-(U4-OFFSET_N1-Pad1)") (class "Default")
      (node (ref "U4") (pin "1") (pinfunction "OFFSET_N1_1") (pintype "input+no_connect"))
    )
    (net (code "131") (name "unconnected-(U4-OFFSET_N2-Pad5)") (class "Default")
      (node (ref "U4") (pin "5") (pinfunction "OFFSET_N2_5") (pintype "input+no_connect"))
    )
  )
)
